# dac.net
KiCad netlist of a schematic drawn in EAGLE
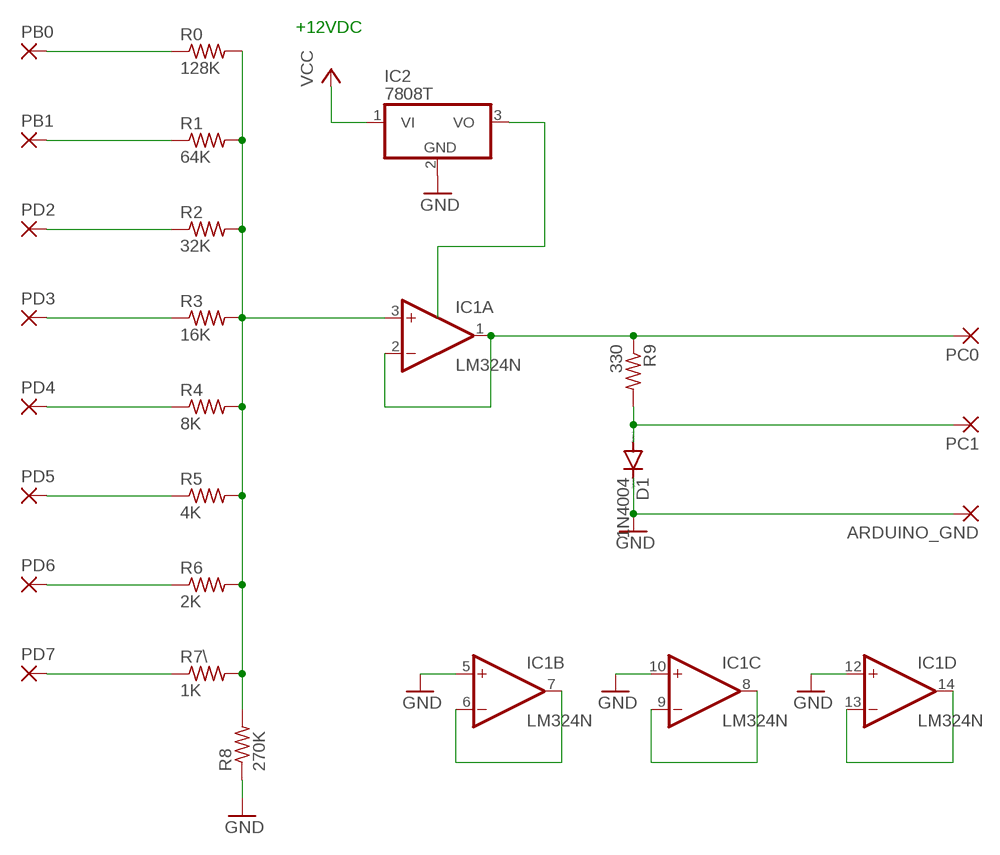
[diagram p0: schematic, sheet 1]

(export (version "E")
  (design (tool "Eeschema 10.0.6"))
  (components
    (comp (ref "ARDUINO_GND")
      (value "1,6/0,8")
      (footprint "eagle-import:1,6_0,8")
      (libsource (lib "eagle-import") (part "1,6/0,8"))
    )
    (comp (ref "D1")
      (value "1N4004")
      (footprint "eagle-import:DO41-10")
      (libsource (lib "eagle-import") (part "1N4004"))
    )
    (comp (ref "IC1")
      (value "LM324N")
      (footprint "eagle-import:DIL14")
      (libsource (lib "eagle-import") (part "LM324N"))
    )
    (comp (ref "IC2")
      (value "7808T")
      (footprint "eagle-import:TO220H")
      (libsource (lib "eagle-import") (part "78T08"))
    )
    (comp (ref "PB0")
      (value "1,6/0,8")
      (footprint "eagle-import:1,6_0,8")
      (libsource (lib "eagle-import") (part "1,6/0,8"))
    )
    (comp (ref "PB1")
      (value "1,6/0,8")
      (footprint "eagle-import:1,6_0,8")
      (libsource (lib "eagle-import") (part "1,6/0,8"))
    )
    (comp (ref "PC0")
      (value "1,6/0,8")
      (footprint "eagle-import:1,6_0,8")
      (libsource (lib "eagle-import") (part "1,6/0,8"))
    )
    (comp (ref "PC1")
      (value "1,6/0,8")
      (footprint "eagle-import:1,6_0,8")
      (libsource (lib "eagle-import") (part "1,6/0,8"))
    )
    (comp (ref "PD2")
      (value "1,6/0,8")
      (footprint "eagle-import:1,6_0,8")
      (libsource (lib "eagle-import") (part "1,6/0,8"))
    )
    (comp (ref "PD3")
      (value "1,6/0,8")
      (footprint "eagle-import:1,6_0,8")
      (libsource (lib "eagle-import") (part "1,6/0,8"))
    )
    (comp (ref "PD4")
      (value "1,6/0,8")
      (footprint "eagle-import:1,6_0,8")
      (libsource (lib "eagle-import") (part "1,6/0,8"))
    )
    (comp (ref "PD5")
      (value "1,6/0,8")
      (footprint "eagle-import:1,6_0,8")
      (libsource (lib "eagle-import") (part "1,6/0,8"))
    )
    (comp (ref "PD6")
      (value "1,6/0,8")
      (footprint "eagle-import:1,6_0,8")
      (libsource (lib "eagle-import") (part "1,6/0,8"))
    )
    (comp (ref "PD7")
      (value "1,6/0,8")
      (footprint "eagle-import:1,6_0,8")
      (libsource (lib "eagle-import") (part "1,6/0,8"))
    )
    (comp (ref "R0")
      (value "128K")
      (footprint "eagle-import:0204_7")
      (libsource (lib "eagle-import") (part "R-US_0204/7"))
    )
    (comp (ref "R1")
      (value "64K")
      (footprint "eagle-import:0204_7")
      (libsource (lib "eagle-import") (part "R-US_0204/7"))
    )
    (comp (ref "R2")
      (value "32K")
      (footprint "eagle-import:0204_7")
      (libsource (lib "eagle-import") (part "R-US_0204/7"))
    )
    (comp (ref "R3")
      (value "16K")
      (footprint "eagle-import:0204_7")
      (libsource (lib "eagle-import") (part "R-US_0204/7"))
    )
    (comp (ref "R4")
      (value "8K")
      (footprint "eagle-import:0204_7")
      (libsource (lib "eagle-import") (part "R-US_0204/7"))
    )
    (comp (ref "R5")
      (value "4K")
      (footprint "eagle-import:0204_7")
      (libsource (lib "eagle-import") (part "R-US_0204/7"))
    )
    (comp (ref "R6")
      (value "2K")
      (footprint "eagle-import:0204_7")
      (libsource (lib "eagle-import") (part "R-US_0204/7"))
    )
    (comp (ref "R7\\")
      (value "1K")
      (footprint "eagle-import:0204_7")
      (libsource (lib "eagle-import") (part "R-US_0204/7"))
    )
    (comp (ref "R8")
      (value "270K")
      (footprint "eagle-import:0204_7")
      (libsource (lib "eagle-import") (part "R-US_0204/7"))
    )
    (comp (ref "R9")
      (value "330")
      (footprint "eagle-import:0204_7")
      (libsource (lib "eagle-import") (part "R-US_0204/7"))
    )
  )
  (nets
    (net (code "1") (name "GND") (class "Default")
      (node (ref "ARDUINO_GND") (pin "1") (pinfunction "P_1") (pintype "passive"))
      (node (ref "D1") (pin "C") (pinfunction "C_C") (pintype "passive"))
      (node (ref "IC1") (pin "10") (pinfunction "+IN_10") (pintype "input"))
      (node (ref "IC1") (pin "12") (pinfunction "+IN_12") (pintype "input"))
      (node (ref "IC1") (pin "5") (pinfunction "+IN_5") (pintype "input"))
      (node (ref "IC2") (pin "2") (pinfunction "GND_2") (pintype "passive"))
      (node (ref "R8") (pin "1") (pinfunction "1_1") (pintype "passive"))
    )
    (net (code "2") (name "Net-(IC1A-+IN)") (class "Default")
      (node (ref "IC1") (pin "3") (pinfunction "+IN_3") (pintype "input"))
      (node (ref "R0") (pin "2") (pinfunction "2_2") (pintype "passive"))
      (node (ref "R1") (pin "2") (pinfunction "2_2") (pintype "passive"))
      (node (ref "R2") (pin "2") (pinfunction "2_2") (pintype "passive"))
      (node (ref "R3") (pin "2") (pinfunction "2_2") (pintype "passive"))
      (node (ref "R4") (pin "2") (pinfunction "2_2") (pintype "passive"))
      (node (ref "R5") (pin "2") (pinfunction "2_2") (pintype "passive"))
      (node (ref "R6") (pin "2") (pinfunction "2_2") (pintype "passive"))
      (node (ref "R7\\") (pin "2") (pinfunction "2_2") (pintype "passive"))
      (node (ref "R8") (pin "2") (pinfunction "2_2") (pintype "passive"))
    )
    (net (code "3") (name "Net-(IC1A--IN)") (class "Default")
      (node (ref "IC1") (pin "1") (pinfunction "OUT_1") (pintype "output"))
      (node (ref "IC1") (pin "2") (pinfunction "-IN_2") (pintype "input"))
      (node (ref "PC0") (pin "1") (pinfunction "P_1") (pintype "passive"))
      (node (ref "R9") (pin "1") (pinfunction "1_1") (pintype "passive"))
    )
    (net (code "4") (name "Net-(IC1B--IN)") (class "Default")
      (node (ref "IC1") (pin "6") (pinfunction "-IN_6") (pintype "input"))
      (node (ref "IC1") (pin "7") (pinfunction "OUT_7") (pintype "output"))
    )
    (net (code "5") (name "Net-(IC1C--IN)") (class "Default")
      (node (ref "IC1") (pin "8") (pinfunction "OUT_8") (pintype "output"))
      (node (ref "IC1") (pin "9") (pinfunction "-IN_9") (pintype "input"))
    )
    (net (code "6") (name "Net-(IC1D--IN)") (class "Default")
      (node (ref "IC1") (pin "13") (pinfunction "-IN_13") (pintype "input"))
      (node (ref "IC1") (pin "14") (pinfunction "OUT_14") (pintype "output"))
    )
    (net (code "7") (name "Net-(PB0-P)") (class "Default")
      (node (ref "PB0") (pin "1") (pinfunction "P_1") (pintype "passive"))
      (node (ref "R0") (pin "1") (pinfunction "1_1") (pintype "passive"))
    )
    (net (code "8") (name "Net-(PB1-P)") (class "Default")
      (node (ref "PB1") (pin "1") (pinfunction "P_1") (pintype "passive"))
      (node (ref "R1") (pin "1") (pinfunction "1_1") (pintype "passive"))
    )
    (net (code "9") (name "Net-(PC1-P)") (class "Default")
      (node (ref "D1") (pin "A") (pinfunction "A_A") (pintype "passive"))
      (node (ref "PC1") (pin "1") (pinfunction "P_1") (pintype "passive"))
      (node (ref "R9") (pin "2") (pinfunction "2_2") (pintype "passive"))
    )
    (net (code "10") (name "Net-(PD2-P)") (class "Default")
      (node (ref "PD2") (pin "1") (pinfunction "P_1") (pintype "passive"))
      (node (ref "R2") (pin "1") (pinfunction "1_1") (pintype "passive"))
    )
    (net (code "11") (name "Net-(PD3-P)") (class "Default")
      (node (ref "PD3") (pin "1") (pinfunction "P_1") (pintype "passive"))
      (node (ref "R3") (pin "1") (pinfunction "1_1") (pintype "passive"))
    )
    (net (code "12") (name "Net-(PD4-P)") (class "Default")
      (node (ref "PD4") (pin "1") (pinfunction "P_1") (pintype "passive"))
      (node (ref "R4") (pin "1") (pinfunction "1_1") (pintype "passive"))
    )
    (net (code "13") (name "Net-(PD5-P)") (class "Default")
      (node (ref "PD5") (pin "1") (pinfunction "P_1") (pintype "passive"))
      (node (ref "R5") (pin "1") (pinfunction "1_1") (pintype "passive"))
    )
    (net (code "14") (name "Net-(PD6-P)") (class "Default")
      (node (ref "PD6") (pin "1") (pinfunction "P_1") (pintype "passive"))
      (node (ref "R6") (pin "1") (pinfunction "1_1") (pintype "passive"))
    )
    (net (code "15") (name "Net-(PD7-P)") (class "Default")
      (node (ref "PD7") (pin "1") (pinfunction "P_1") (pintype "passive"))
      (node (ref "R7\\") (pin "1") (pinfunction "1_1") (pintype "passive"))
    )
    (net (code "16") (name "VCC") (class "Default")
      (node (ref "IC2") (pin "1") (pinfunction "VI_1") (pintype "input"))
    )
    (net (code "17") (name "unconnected-(IC2-VO-Pad3)") (class "Default")
      (node (ref "IC2") (pin "3") (pinfunction "VO_3") (pintype "passive"))
    )
  )
)
